# serpentine2.net
KiCad netlist of a schematic drawn in Altium Designer
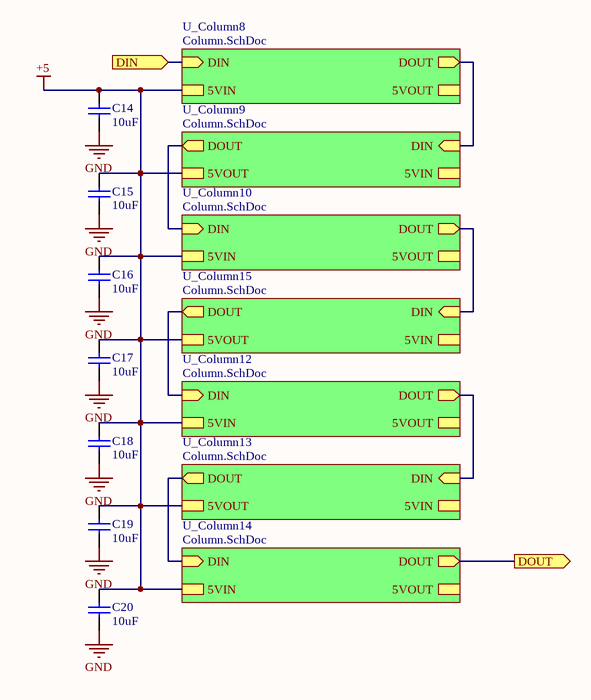
[diagram p0: serpentine2.SchDoc]

(export (version "E")
  (design (tool "Eeschema 10.0.6"))
  (components
    (comp (ref "C14")
      (value "10uF")
      (footprint "CAP0603")
      (description "C342827")
      (fields (field (name "TOLERANCE") "10%"))
      (libsource (lib "blandat") (part "CAP"))
    )
    (comp (ref "C15")
      (value "10uF")
      (footprint "CAP1206")
      (description "C342827")
      (fields (field (name "TOLERANCE") "10%"))
      (libsource (lib "blandat") (part "CAP"))
    )
    (comp (ref "C16")
      (value "10uF")
      (footprint "CAP1206")
      (description "C342827")
      (fields (field (name "TOLERANCE") "10%"))
      (libsource (lib "blandat") (part "CAP"))
    )
    (comp (ref "C17")
      (value "10uF")
      (footprint "CAP1206")
      (description "C342827")
      (fields (field (name "TOLERANCE") "10%"))
      (libsource (lib "blandat") (part "CAP"))
    )
    (comp (ref "C18")
      (value "10uF")
      (footprint "CAP1206")
      (description "C342827")
      (fields (field (name "TOLERANCE") "10%"))
      (libsource (lib "blandat") (part "CAP"))
    )
    (comp (ref "C19")
      (value "10uF")
      (footprint "CAP1206")
      (description "C342827")
      (fields (field (name "TOLERANCE") "10%"))
      (libsource (lib "blandat") (part "CAP"))
    )
    (comp (ref "C20")
      (value "10uF")
      (footprint "CAP1206")
      (description "C342827")
      (fields (field (name "TOLERANCE") "10%"))
      (libsource (lib "blandat") (part "CAP"))
    )
  )
  (nets
    (net (code "1") (name "+5") (class "Default")
      (node (ref "C14") (pin "2") (pinfunction "2_2") (pintype "passive"))
      (node (ref "C15") (pin "2") (pinfunction "2_2") (pintype "passive"))
      (node (ref "C16") (pin "2") (pinfunction "2_2") (pintype "passive"))
      (node (ref "C17") (pin "2") (pinfunction "2_2") (pintype "passive"))
      (node (ref "C18") (pin "2") (pinfunction "2_2") (pintype "passive"))
      (node (ref "C19") (pin "2") (pinfunction "2_2") (pintype "passive"))
      (node (ref "C20") (pin "2") (pinfunction "2_2") (pintype "passive"))
    )
    (net (code "17") (name "GND") (class "Default")
      (node (ref "C14") (pin "1") (pinfunction "1_1") (pintype "passive"))
      (node (ref "C15") (pin "1") (pinfunction "1_1") (pintype "passive"))
      (node (ref "C16") (pin "1") (pinfunction "1_1") (pintype "passive"))
      (node (ref "C17") (pin "1") (pinfunction "1_1") (pintype "passive"))
      (node (ref "C18") (pin "1") (pinfunction "1_1") (pintype "passive"))
      (node (ref "C19") (pin "1") (pinfunction "1_1") (pintype "passive"))
      (node (ref "C20") (pin "1") (pinfunction "1_1") (pintype "passive"))
    )
  )
)
